# AIRZAI_BASE_BD_REVA_Sheet2.net
KiCad netlist of a schematic drawn in Altium Designer
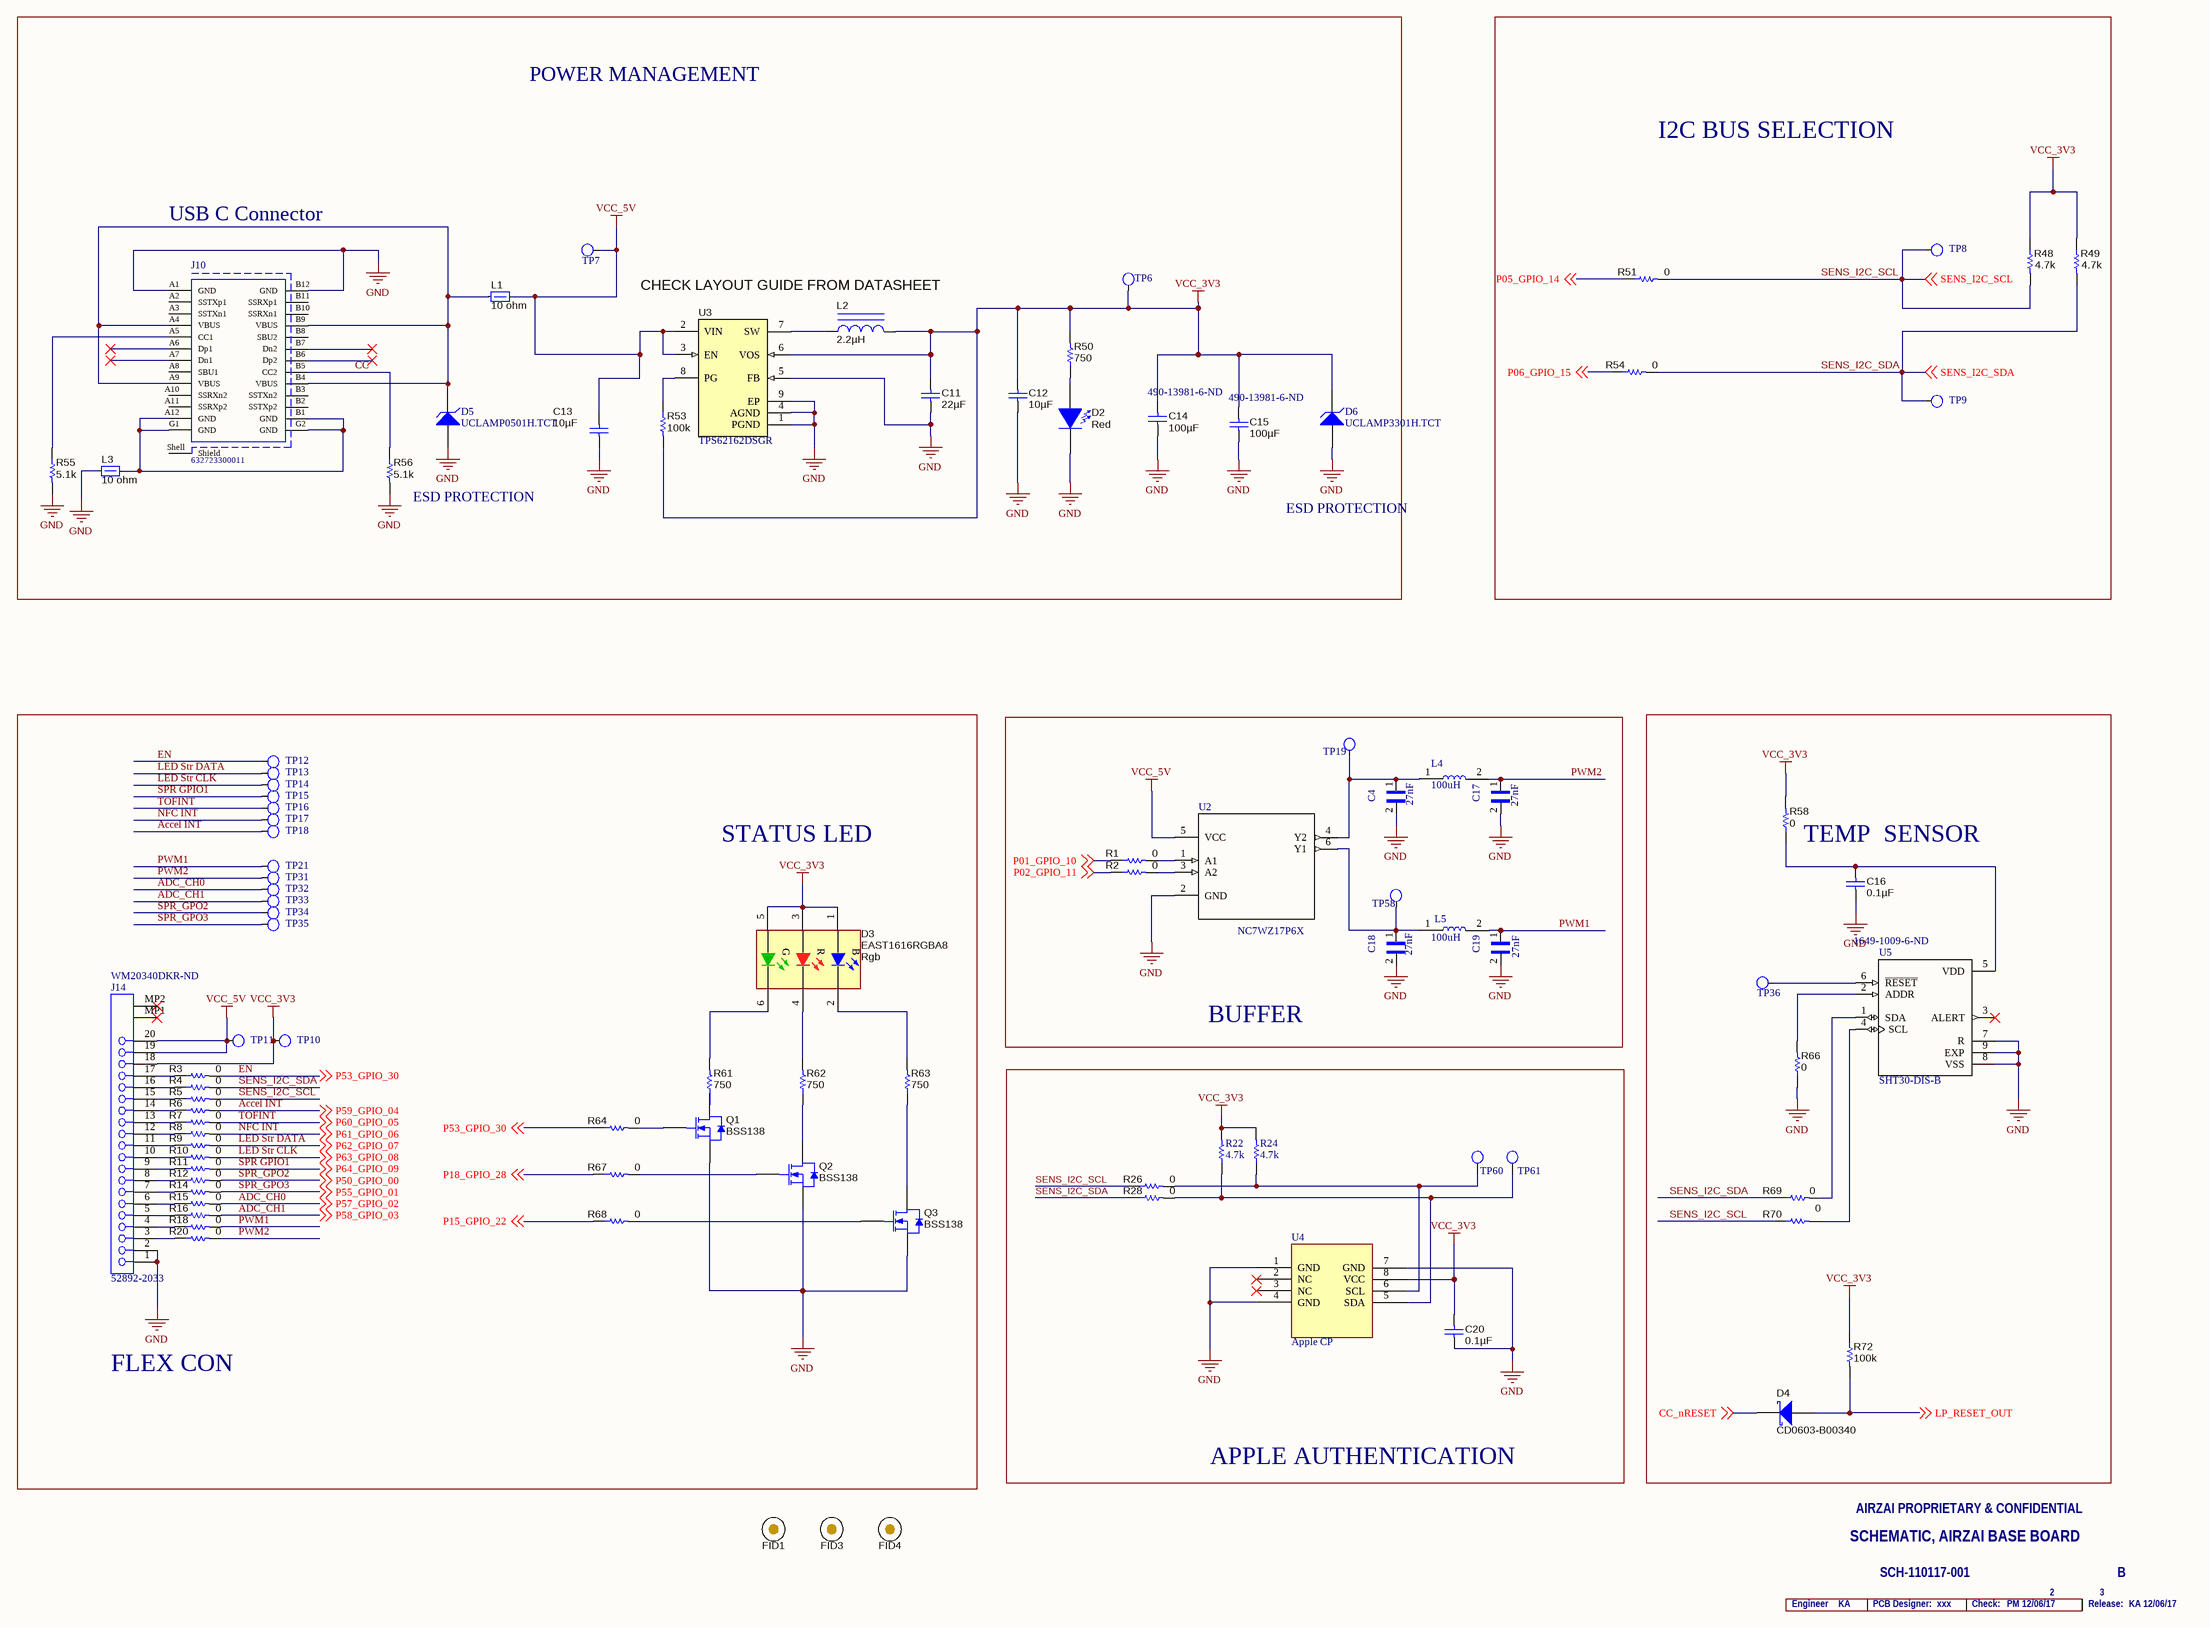
[diagram p0: AIRZAI_BASE_BD_REVA Sheet2.SchDoc]

(export (version "E")
  (design (tool "Eeschema 10.0.6"))
  (components
    (comp (ref "C4")
      (value "27nF")
      (footprint "1206CAP")
      (description "1206 27 nF 50 V Â±5% Tolerance C0G SMT Multilayer Ceramic Capacitor")
      (fields (field (name "MF") "Murata Electronics") (field (name "MP") "GRM3195C1H273JA01D"))
      (libsource (lib "GRM3195C1H273JA01D") (part "GRM3195C1H273JA01D"))
    )
    (comp (ref "C11")
      (value "C2012X5R1C226K125AC")
      (footprint "0805_HV")
      (description "CAP, CERM, 22 µF, 16 V, +/- 10%, X5R, 0805")
      (fields
        (field (name "VALUEDISPLAYED") "22µF")
        (field (name "MANUFACTURER") "TDK")
        (field (name "PUBLISHER") "Texas Instruments")
      )
      (libsource (lib "Capacitor_Ceramic") (part "C2012X5R1C226K125AC"))
    )
    (comp (ref "C12")
      (value "GRM21BR61A106KE19L")
      (footprint "0805_HV")
      (description "CAP, CERM, 10 µF, 10 V, +/- 10%, X5R, 0805")
      (fields
        (field (name "VALUEDISPLAYED") "10µF")
        (field (name "MANUFACTURER") "MuRata")
        (field (name "PUBLISHER") "Texas Instruments")
      )
      (libsource (lib "Capacitor_Ceramic") (part "GRM21BR61A106KE19L"))
    )
    (comp (ref "C13")
      (value "GRM21BR61A106KE19L")
      (footprint "0805_HV")
      (description "CAP, CERM, 10 µF, 10 V, +/- 10%, X5R, 0805")
      (fields
        (field (name "VALUEDISPLAYED") "10µF")
        (field (name "MANUFACTURER") "MuRata")
        (field (name "PUBLISHER") "Texas Instruments")
      )
      (libsource (lib "Capacitor_Ceramic") (part "GRM21BR61A106KE19L"))
    )
    (comp (ref "C14")
      (value "GRM31CR60J107ME39L")
      (footprint "1206_180")
      (description "CAP, CERM, 100 µF, 6.3 V, +/- 20%, X5R, 1206")
      (fields
        (field (name "VALUEDISPLAYED") "100µF")
        (field (name "MANUFACTURER") "MuRata")
        (field (name "SUPPLIER PART NUMBER 3") "490-13981-6-ND")
        (field (name "PUBLISHER") "Texas Instruments")
      )
      (libsource (lib "Capacitor_Ceramic") (part "GRM31CR60J107ME39L"))
    )
    (comp (ref "C15")
      (value "GRM31CR60J107ME39L")
      (footprint "1206_180")
      (description "CAP, CERM, 100 µF, 6.3 V, +/- 20%, X5R, 1206")
      (fields
        (field (name "VALUEDISPLAYED") "100µF")
        (field (name "MANUFACTURER") "MuRata")
        (field (name "SUPPLIER PART NUMBER 3") "490-13981-6-ND")
        (field (name "PUBLISHER") "Texas Instruments")
      )
      (libsource (lib "Capacitor_Ceramic") (part "GRM31CR60J107ME39L"))
    )
    (comp (ref "C16")
      (value "GRM155R61A104KA01D")
      (footprint "0402")
      (description "CAP, CERM, 0.1 µF, 10 V, +/- 10%, X5R, 0402")
      (fields
        (field (name "VALUEDISPLAYED") "0.1µF")
        (field (name "MANUFACTURER") "MuRata")
        (field (name "PUBLISHER") "Texas Instruments")
      )
      (libsource (lib "Capacitor_Ceramic") (part "GRM155R61A104KA01D"))
    )
    (comp (ref "C17")
      (value "27nF")
      (footprint "1206CAP")
      (description "1206 27 nF 50 V Â±5% Tolerance C0G SMT Multilayer Ceramic Capacitor")
      (fields (field (name "MF") "Murata Electronics") (field (name "MP") "GRM3195C1H273JA01D"))
      (libsource (lib "GRM3195C1H273JA01D") (part "GRM3195C1H273JA01D"))
    )
    (comp (ref "C18")
      (value "27nF")
      (footprint "1206CAP")
      (description "1206 27 nF 50 V Â±5% Tolerance C0G SMT Multilayer Ceramic Capacitor")
      (fields (field (name "MF") "Murata Electronics") (field (name "MP") "GRM3195C1H273JA01D"))
      (libsource (lib "GRM3195C1H273JA01D") (part "GRM3195C1H273JA01D"))
    )
    (comp (ref "C19")
      (value "27nF")
      (footprint "1206CAP")
      (description "1206 27 nF 50 V Â±5% Tolerance C0G SMT Multilayer Ceramic Capacitor")
      (fields (field (name "MF") "Murata Electronics") (field (name "MP") "GRM3195C1H273JA01D"))
      (libsource (lib "GRM3195C1H273JA01D") (part "GRM3195C1H273JA01D"))
    )
    (comp (ref "C20")
      (value "C1005X5R1A104K050BA")
      (footprint "SM0402_BTD.1SM_ACT_H55_CAP_WSS")
      (description "CAP, CERM, 0.1 µF, 10 V, +/- 10%, X5R, 0402")
      (fields
        (field (name "MANUFACTURER") "TDK")
        (field (name "VALUEDISPLAYED") "0.1µF")
        (field (name "PUBLISHER") "Texas Instruments")
      )
      (libsource (lib "AIRZAI_MBD_REVB2") (part "C1005X5R1A104K050BA"))
    )
    (comp (ref "D2")
      (value "Red")
      (footprint "SML-31_Red")
      (description "LED, Red, SMD")
      (fields
        (field (name "MANUFACTURER") "Rohm")
        (field (name "PARTNUMBER") "SML-311UTT86")
        (field (name "PUBLISHER") "Texas Instruments")
      )
      (libsource (lib "LED") (part "SML-311UTT86"))
    )
    (comp (ref "D3")
      (value "EAST1616RGBA8")
      (footprint "EAST1616_RGB")
      (description "LED, Rgb, SMD")
      (fields
        (field (name "ALTIUM_VALUE") "Rgb")
        (field (name "MANUFACTURER") "Everlight")
        (field (name "SYMBOLCREATOR") "Altium")
        (field (name "PUBLISHER") "Texas Instruments")
      )
      (libsource (lib "LED") (part "EAST1616RGBA8"))
    )
    (comp (ref "D4")
      (value "CD0603-B00340")
      (footprint "Diode_0603")
      (description "Diode, Schottky, 45 V, 0.03 A, 0603 Diode")
      (fields (field (name "MANUFACTURER") "Bourns") (field (name "PUBLISHER") "Texas Instruments"))
      (libsource (lib "Diode") (part "CD0603-B00340"))
    )
    (comp (ref "D5")
      (value "UCLAMP0501H.TCT")
      (footprint "SOD-523")
      (description "TVS DIODE 5V 12.5V SOD523")
      (fields (field (name "MANUFACTURER") "Semtech"))
      (libsource (lib "AIRZAI_BASE_BD_REVA") (part "UCLAMP0501H.TCT"))
    )
    (comp (ref "D6")
      (value "UCLAMP3301H.TCT")
      (footprint "SOD-523")
      (description "TVS DIODE 3.3V 8V SOD523")
      (fields (field (name "MANUFACTURER") "Semtech"))
      (libsource (lib "AIRZAI_BASE_BD_REVA") (part "UCLAMP3301H.TCT"))
    )
    (comp (ref "FID1")
      (value "Fiducial")
      (footprint "Fiducial10-20")
      (description "Fiducial mark.  There is nothing to buy or mount.")
      (fields (field (name "SYMBOLCREATOR") "codlsc") (field (name "PUBLISHER") "Texas Instruments"))
      (libsource (lib "MiscParts") (part "Fiducial"))
    )
    (comp (ref "FID3")
      (value "Fiducial")
      (footprint "Fiducial10-20")
      (description "Fiducial mark.  There is nothing to buy or mount.")
      (fields (field (name "SYMBOLCREATOR") "codlsc") (field (name "PUBLISHER") "Texas Instruments"))
      (libsource (lib "MiscParts") (part "Fiducial"))
    )
    (comp (ref "FID4")
      (value "Fiducial")
      (footprint "Fiducial10-20")
      (description "Fiducial mark.  There is nothing to buy or mount.")
      (fields (field (name "SYMBOLCREATOR") "codlsc") (field (name "PUBLISHER") "Texas Instruments"))
      (libsource (lib "MiscParts") (part "Fiducial"))
    )
    (comp (ref "J10")
      (value "632723300011")
      (footprint "632723300011")
      (description "USB 3.1 Type C Receptacle WR-COM, Horizontal, SMT / THT")
      (fields (field (name "PUBLISHER") "Wurth Elektronik"))
      (libsource (lib "Altium_WR-COM_USB-Connectors (rev18b)") (part "632723300011"))
    )
    (comp (ref "J14")
      (value "52892-2033")
      (footprint "MOLX-52892-2033")
      (fields (field (name "MANUFACTURER") "Molex") (field (name "SUPPLIER PART NUMBER 1") "WM20340DKR-ND"))
      (libsource (lib "Altium Content Vault") (part "MOLX-52892-2033"))
    )
    (comp (ref "L1")
      (value "10 ohm")
      (footprint "0402")
      (description "Ferrite Bead, 10 ohm @ 100 MHz, 1 A, 0402")
      (fields
        (field (name "PARTNUMBER") "BLM15AG100SN1D")
        (field (name "MANUFACTURER") "MuRata")
        (field (name "PUBLISHER") "Texas Instruments")
      )
      (libsource (lib "FerriteBead") (part "BLM15AG100SN1D"))
    )
    (comp (ref "L2")
      (value "BRC2012T2R2MD")
      (footprint "0805_HV")
      (description "Inductor, Wirewound, 2.2 µH, 1 A, 0.143 ohm, SMD")
      (fields
        (field (name "VALUEDISPLAYED") "2.2µH")
        (field (name "MANUFACTURER") "Taiyo Yuden")
        (field (name "PUBLISHER") "Texas Instruments")
      )
      (libsource (lib "Inductor_Other") (part "BRC2012T2R2MD"))
    )
    (comp (ref "L3")
      (value "10 ohm")
      (footprint "0402")
      (description "Ferrite Bead, 10 ohm @ 100 MHz, 1 A, 0402")
      (fields
        (field (name "PARTNUMBER") "BLM15AG100SN1D")
        (field (name "MANUFACTURER") "MuRata")
        (field (name "PUBLISHER") "Texas Instruments")
      )
      (libsource (lib "") (part "BLM15AG100SN1D_1"))
    )
    (comp (ref "L4")
      (value "100uH")
      (footprint "0805_Inductor")
      (description "Fixed Ind 100uh 2ma 3.1 Ohm Smd")
      (fields (field (name "MP") "MLF2012C101KTD25") (field (name "MF") "TDK"))
      (libsource (lib "MLF2012C101KTD25") (part "MLF2012C101KTD25"))
    )
    (comp (ref "L5")
      (value "100uH")
      (footprint "0805_Inductor")
      (description "Fixed Ind 100uh 2ma 3.1 Ohm Smd")
      (fields (field (name "MP") "MLF2012C101KTD25") (field (name "MF") "TDK"))
      (libsource (lib "MLF2012C101KTD25") (part "MLF2012C101KTD25"))
    )
    (comp (ref "Q1")
      (value "BSS138")
      (footprint "SOT-23")
      (description "MOSFET, N-CH, 50 V, 0.22 A, SOT-23")
      (fields
        (field (name "MANUFACTURER") "Fairchild Semiconductor")
        (field (name "PUBLISHER") "Texas Instruments")
      )
      (libsource (lib "FETs") (part "BSS138"))
    )
    (comp (ref "Q2")
      (value "BSS138")
      (footprint "SOT-23")
      (description "MOSFET, N-CH, 50 V, 0.22 A, SOT-23")
      (fields
        (field (name "MANUFACTURER") "Fairchild Semiconductor")
        (field (name "PUBLISHER") "Texas Instruments")
      )
      (libsource (lib "FETs") (part "BSS138"))
    )
    (comp (ref "Q3")
      (value "BSS138")
      (footprint "SOT-23")
      (description "MOSFET, N-CH, 50 V, 0.22 A, SOT-23")
      (fields
        (field (name "MANUFACTURER") "Fairchild Semiconductor")
        (field (name "PUBLISHER") "Texas Instruments")
      )
      (libsource (lib "FETs") (part "BSS138"))
    )
    (comp (ref "R1")
      (value "ERJ-2GE0R00X")
      (footprint "0402")
      (description "RES, 0, 5%, 0.063 W, 0402")
      (fields
        (field (name "VALUEDISPLAYED") "0")
        (field (name "MANUFACTURER") "Panasonic")
        (field (name "DIGI-KEY_PART_NUMBER") "P0.0JCT-ND")
        (field (name "PUBLISHER") "Texas Instruments")
      )
      (libsource (lib "Resistor_0402") (part "ERJ-2GE0R00X"))
    )
    (comp (ref "R2")
      (value "ERJ-2GE0R00X")
      (footprint "0402")
      (description "RES, 0, 5%, 0.063 W, 0402")
      (fields
        (field (name "VALUEDISPLAYED") "0")
        (field (name "MANUFACTURER") "Panasonic")
        (field (name "DIGI-KEY_PART_NUMBER") "P0.0JCT-ND")
        (field (name "PUBLISHER") "Texas Instruments")
      )
      (libsource (lib "Resistor_0402") (part "ERJ-2GE0R00X"))
    )
    (comp (ref "R3")
      (value "ERJ-2GE0R00X")
      (footprint "0402")
      (description "RES, 0, 5%, 0.063 W, 0402")
      (fields
        (field (name "VALUEDISPLAYED") "0")
        (field (name "MANUFACTURER") "Panasonic")
        (field (name "PUBLISHER") "Texas Instruments")
      )
      (libsource (lib "Resistor_0402") (part "ERJ-2GE0R00X"))
    )
    (comp (ref "R4")
      (value "ERJ-2GE0R00X")
      (footprint "0402")
      (description "RES, 0, 5%, 0.063 W, 0402")
      (fields
        (field (name "VALUEDISPLAYED") "0")
        (field (name "MANUFACTURER") "Panasonic")
        (field (name "PUBLISHER") "Texas Instruments")
      )
      (libsource (lib "Resistor_0402") (part "ERJ-2GE0R00X"))
    )
    (comp (ref "R5")
      (value "ERJ-2GE0R00X")
      (footprint "0402")
      (description "RES, 0, 5%, 0.063 W, 0402")
      (fields
        (field (name "VALUEDISPLAYED") "0")
        (field (name "MANUFACTURER") "Panasonic")
        (field (name "PUBLISHER") "Texas Instruments")
      )
      (libsource (lib "Resistor_0402") (part "ERJ-2GE0R00X"))
    )
    (comp (ref "R6")
      (value "ERJ-2GE0R00X")
      (footprint "0402")
      (description "RES, 0, 5%, 0.063 W, 0402")
      (fields
        (field (name "VALUEDISPLAYED") "0")
        (field (name "MANUFACTURER") "Panasonic")
        (field (name "PUBLISHER") "Texas Instruments")
      )
      (libsource (lib "Resistor_0402") (part "ERJ-2GE0R00X"))
    )
    (comp (ref "R7")
      (value "ERJ-2GE0R00X")
      (footprint "0402")
      (description "RES, 0, 5%, 0.063 W, 0402")
      (fields
        (field (name "VALUEDISPLAYED") "0")
        (field (name "MANUFACTURER") "Panasonic")
        (field (name "PUBLISHER") "Texas Instruments")
      )
      (libsource (lib "Resistor_0402") (part "ERJ-2GE0R00X"))
    )
    (comp (ref "R8")
      (value "ERJ-2GE0R00X")
      (footprint "0402")
      (description "RES, 0, 5%, 0.063 W, 0402")
      (fields
        (field (name "VALUEDISPLAYED") "0")
        (field (name "MANUFACTURER") "Panasonic")
        (field (name "PUBLISHER") "Texas Instruments")
      )
      (libsource (lib "Resistor_0402") (part "ERJ-2GE0R00X"))
    )
    (comp (ref "R9")
      (value "ERJ-2GE0R00X")
      (footprint "0402")
      (description "RES, 0, 5%, 0.063 W, 0402")
      (fields
        (field (name "VALUEDISPLAYED") "0")
        (field (name "MANUFACTURER") "Panasonic")
        (field (name "PUBLISHER") "Texas Instruments")
      )
      (libsource (lib "Resistor_0402") (part "ERJ-2GE0R00X"))
    )
    (comp (ref "R10")
      (value "ERJ-2GE0R00X")
      (footprint "0402")
      (description "RES, 0, 5%, 0.063 W, 0402")
      (fields
        (field (name "VALUEDISPLAYED") "0")
        (field (name "MANUFACTURER") "Panasonic")
        (field (name "PUBLISHER") "Texas Instruments")
      )
      (libsource (lib "Resistor_0402") (part "ERJ-2GE0R00X"))
    )
    (comp (ref "R11")
      (value "ERJ-2GE0R00X")
      (footprint "0402")
      (description "RES, 0, 5%, 0.063 W, 0402")
      (fields
        (field (name "VALUEDISPLAYED") "0")
        (field (name "MANUFACTURER") "Panasonic")
        (field (name "PUBLISHER") "Texas Instruments")
      )
      (libsource (lib "Resistor_0402") (part "ERJ-2GE0R00X"))
    )
    (comp (ref "R12")
      (value "ERJ-2GE0R00X")
      (footprint "0402")
      (description "RES, 0, 5%, 0.063 W, 0402")
      (fields
        (field (name "VALUEDISPLAYED") "0")
        (field (name "MANUFACTURER") "Panasonic")
        (field (name "PUBLISHER") "Texas Instruments")
      )
      (libsource (lib "Resistor_0402") (part "ERJ-2GE0R00X"))
    )
    (comp (ref "R14")
      (value "ERJ-2GE0R00X")
      (footprint "0402")
      (description "RES, 0, 5%, 0.063 W, 0402")
      (fields
        (field (name "VALUEDISPLAYED") "0")
        (field (name "MANUFACTURER") "Panasonic")
        (field (name "PUBLISHER") "Texas Instruments")
      )
      (libsource (lib "Resistor_0402") (part "ERJ-2GE0R00X"))
    )
    (comp (ref "R15")
      (value "ERJ-2GE0R00X")
      (footprint "0402")
      (description "RES, 0, 5%, 0.063 W, 0402")
      (fields
        (field (name "VALUEDISPLAYED") "0")
        (field (name "MANUFACTURER") "Panasonic")
        (field (name "PUBLISHER") "Texas Instruments")
      )
      (libsource (lib "Resistor_0402") (part "ERJ-2GE0R00X"))
    )
    (comp (ref "R16")
      (value "ERJ-2GE0R00X")
      (footprint "0402")
      (description "RES, 0, 5%, 0.063 W, 0402")
      (fields
        (field (name "VALUEDISPLAYED") "0")
        (field (name "MANUFACTURER") "Panasonic")
        (field (name "PUBLISHER") "Texas Instruments")
      )
      (libsource (lib "Resistor_0402") (part "ERJ-2GE0R00X"))
    )
    (comp (ref "R18")
      (value "ERJ-2GE0R00X")
      (footprint "0402")
      (description "RES, 0, 5%, 0.063 W, 0402")
      (fields
        (field (name "VALUEDISPLAYED") "0")
        (field (name "MANUFACTURER") "Panasonic")
        (field (name "PUBLISHER") "Texas Instruments")
      )
      (libsource (lib "Resistor_0402") (part "ERJ-2GE0R00X"))
    )
    (comp (ref "R20")
      (value "ERJ-2GE0R00X")
      (footprint "0402")
      (description "RES, 0, 5%, 0.063 W, 0402")
      (fields
        (field (name "VALUEDISPLAYED") "0")
        (field (name "MANUFACTURER") "Panasonic")
        (field (name "PUBLISHER") "Texas Instruments")
      )
      (libsource (lib "Resistor_0402") (part "ERJ-2GE0R00X"))
    )
    (comp (ref "R22")
      (value "RMCF0402JT4K70")
      (footprint "0402")
      (description "Chip Resistor, 4.7 KOhm, +/- 5%, 0.063 W, -55 to 155 degC, 0402 (1005 Metric), RoHS, Tape and Reel")
      (fields
        (field (name "MANUFACTURER") "Stackpole-Electronics-Inc.")
        (field (name "TOLERANCE") "±5%")
        (field (name "RESISTANCE (OHMS)") "4.7k")
      )
      (libsource (lib "AIRZAI_BASE_BD_REVA") (part "RES-2"))
    )
    (comp (ref "R24")
      (value "RMCF0402JT4K70")
      (footprint "0402")
      (description "Chip Resistor, 4.7 KOhm, +/- 5%, 0.063 W, -55 to 155 degC, 0402 (1005 Metric), RoHS, Tape and Reel")
      (fields
        (field (name "MANUFACTURER") "Stackpole-Electronics-Inc.")
        (field (name "TOLERANCE") "±5%")
        (field (name "RESISTANCE (OHMS)") "4.7k")
      )
      (libsource (lib "AIRZAI_BASE_BD_REVA") (part "RES-2"))
    )
    (comp (ref "R26")
      (value "ERJ-2GE0R00X")
      (footprint "0402")
      (description "RES, 0, 5%, 0.063 W, 0402")
      (fields
        (field (name "VALUEDISPLAYED") "0")
        (field (name "MANUFACTURER") "Panasonic")
        (field (name "DIGI-KEY_PART_NUMBER") "P0.0JCT-ND")
        (field (name "PUBLISHER") "Texas Instruments")
      )
      (libsource (lib "Resistor_0402") (part "ERJ-2GE0R00X"))
    )
    (comp (ref "R28")
      (value "ERJ-2GE0R00X")
      (footprint "0402")
      (description "RES, 0, 5%, 0.063 W, 0402")
      (fields
        (field (name "VALUEDISPLAYED") "0")
        (field (name "MANUFACTURER") "Panasonic")
        (field (name "DIGI-KEY_PART_NUMBER") "P0.0JCT-ND")
        (field (name "PUBLISHER") "Texas Instruments")
      )
      (libsource (lib "Resistor_0402") (part "ERJ-2GE0R00X"))
    )
    (comp (ref "R48")
      (value "4.7k")
      (footprint "0402")
      (description "RES SMD 4.7K OHM 1% 1/16W 0402")
      (fields
        (field (name "MANUFACTURER") "Yageo")
        (field (name "MANUFACTURER PART NUMBER") "RC0402FR-074K7L")
      )
      (libsource (lib "Resistor_0402") (part "CRCW04023K30JNED"))
    )
    (comp (ref "R49")
      (value "4.7k")
      (footprint "0402")
      (description "RES SMD 4.7K OHM 1% 1/16W 0402")
      (fields
        (field (name "MANUFACTURER") "Yageo")
        (field (name "MANUFACTURER PART NUMBER") "RC0402FR-074K7L")
      )
      (libsource (lib "Resistor_0402") (part "CRCW04023K30JNED"))
    )
    (comp (ref "R50")
      (value "RC0603JR-07750RL")
      (footprint "0603")
      (description "RES, 750, 5%, 0.1 W, 0603")
      (fields
        (field (name "VALUEDISPLAYED") "750")
        (field (name "MANUFACTURER") "Yageo America")
        (field (name "PUBLISHER") "Texas Instruments")
      )
      (libsource (lib "Resistor_0603") (part "RC0603JR-07750RL"))
    )
    (comp (ref "R51")
      (value "ERJ-2GE0R00X")
      (footprint "0402")
      (description "RES, 0, 5%, 0.063 W, 0402")
      (fields
        (field (name "VALUEDISPLAYED") "0")
        (field (name "MANUFACTURER") "Panasonic")
        (field (name "PUBLISHER") "Texas Instruments")
      )
      (libsource (lib "Resistor_0402") (part "ERJ-2GE0R00X"))
    )
    (comp (ref "R53")
      (value "CRCW0402100KJNED")
      (footprint "0402")
      (description "RES, 100 k, 5%, 0.063 W, 0402")
      (fields
        (field (name "VALUEDISPLAYED") "100k")
        (field (name "MANUFACTURER") "Vishay-Dale")
        (field (name "PUBLISHER") "Texas Instruments")
      )
      (libsource (lib "Resistor_0402") (part "CRCW0402100KJNED"))
    )
    (comp (ref "R54")
      (value "ERJ-2GE0R00X")
      (footprint "0402")
      (description "RES, 0, 5%, 0.063 W, 0402")
      (fields
        (field (name "VALUEDISPLAYED") "0")
        (field (name "MANUFACTURER") "Panasonic")
        (field (name "PUBLISHER") "Texas Instruments")
      )
      (libsource (lib "Resistor_0402") (part "ERJ-2GE0R00X"))
    )
    (comp (ref "R55")
      (value "CRCW040210K0JNED")
      (footprint "0402")
      (description "RES, 10 k, 5%, 0.063 W, 0402")
      (fields
        (field (name "VALUEDISPLAYED") "5.1k")
        (field (name "MANUFACTURER") "Vishay-Dale")
        (field (name "PUBLISHER") "Texas Instruments")
      )
      (libsource (lib "Resistor_0402") (part "CRCW040210K0JNED"))
    )
    (comp (ref "R56")
      (value "CRCW040210K0JNED")
      (footprint "0402")
      (description "RES, 10 k, 5%, 0.063 W, 0402")
      (fields
        (field (name "VALUEDISPLAYED") "5.1k")
        (field (name "MANUFACTURER") "Vishay-Dale")
        (field (name "PUBLISHER") "Texas Instruments")
      )
      (libsource (lib "Resistor_0402") (part "CRCW040210K0JNED"))
    )
    (comp (ref "R58")
      (value "ERJ-2GE0R00X")
      (footprint "0402")
      (description "RES, 0, 5%, 0.063 W, 0402")
      (fields
        (field (name "VALUEDISPLAYED") "0")
        (field (name "MANUFACTURER") "Panasonic")
        (field (name "PUBLISHER") "Texas Instruments")
      )
      (libsource (lib "Resistor_0402") (part "ERJ-2GE0R00X"))
    )
    (comp (ref "R61")
      (value "RC0603JR-07750RL")
      (footprint "0603")
      (description "RES, 750, 5%, 0.1 W, 0603")
      (fields
        (field (name "VALUEDISPLAYED") "750")
        (field (name "MANUFACTURER") "Yageo America")
        (field (name "PUBLISHER") "Texas Instruments")
      )
      (libsource (lib "Resistor_0603") (part "RC0603JR-07750RL"))
    )
    (comp (ref "R62")
      (value "RC0603JR-07750RL")
      (footprint "0603")
      (description "RES, 750, 5%, 0.1 W, 0603")
      (fields
        (field (name "VALUEDISPLAYED") "750")
        (field (name "MANUFACTURER") "Yageo America")
        (field (name "PUBLISHER") "Texas Instruments")
      )
      (libsource (lib "Resistor_0603") (part "RC0603JR-07750RL"))
    )
    (comp (ref "R63")
      (value "RC0603JR-07750RL")
      (footprint "0603")
      (description "RES, 750, 5%, 0.1 W, 0603")
      (fields
        (field (name "VALUEDISPLAYED") "750")
        (field (name "MANUFACTURER") "Yageo America")
        (field (name "PUBLISHER") "Texas Instruments")
      )
      (libsource (lib "Resistor_0603") (part "RC0603JR-07750RL"))
    )
    (comp (ref "R64")
      (value "ERJ-2GE0R00X")
      (footprint "0402")
      (description "RES, 0, 5%, 0.063 W, 0402")
      (fields
        (field (name "VALUEDISPLAYED") "0")
        (field (name "MANUFACTURER") "Panasonic")
        (field (name "PUBLISHER") "Texas Instruments")
      )
      (libsource (lib "Resistor_0402") (part "ERJ-2GE0R00X"))
    )
    (comp (ref "R66")
      (value "ERJ-2GE0R00X")
      (footprint "0402")
      (description "RES, 0, 5%, 0.063 W, 0402")
      (fields
        (field (name "VALUEDISPLAYED") "0")
        (field (name "MANUFACTURER") "Panasonic")
        (field (name "PUBLISHER") "Texas Instruments")
      )
      (libsource (lib "Resistor_0402") (part "ERJ-2GE0R00X"))
    )
    (comp (ref "R67")
      (value "ERJ-2GE0R00X")
      (footprint "0402")
      (description "RES, 0, 5%, 0.063 W, 0402")
      (fields
        (field (name "VALUEDISPLAYED") "0")
        (field (name "MANUFACTURER") "Panasonic")
        (field (name "PUBLISHER") "Texas Instruments")
      )
      (libsource (lib "Resistor_0402") (part "ERJ-2GE0R00X"))
    )
    (comp (ref "R68")
      (value "ERJ-2GE0R00X")
      (footprint "0402")
      (description "RES, 0, 5%, 0.063 W, 0402")
      (fields
        (field (name "VALUEDISPLAYED") "0")
        (field (name "MANUFACTURER") "Panasonic")
        (field (name "PUBLISHER") "Texas Instruments")
      )
      (libsource (lib "Resistor_0402") (part "ERJ-2GE0R00X"))
    )
    (comp (ref "R69")
      (value "ERJ-2GE0R00X")
      (footprint "0402")
      (description "RES, 0, 5%, 0.063 W, 0402")
      (fields
        (field (name "VALUEDISPLAYED") "0")
        (field (name "MANUFACTURER") "Panasonic")
        (field (name "PUBLISHER") "Texas Instruments")
      )
      (libsource (lib "Resistor_0402") (part "ERJ-2GE0R00X"))
    )
    (comp (ref "R70")
      (value "ERJ-2GE0R00X")
      (footprint "0402")
      (description "RES, 0, 5%, 0.063 W, 0402")
      (fields
        (field (name "VALUEDISPLAYED") "0")
        (field (name "MANUFACTURER") "Panasonic")
        (field (name "PUBLISHER") "Texas Instruments")
      )
      (libsource (lib "Resistor_0402") (part "ERJ-2GE0R00X"))
    )
    (comp (ref "R72")
      (value "CRCW0402100KJNED")
      (footprint "0402")
      (description "RES, 100 k, 5%, 0.063 W, 0402")
      (fields
        (field (name "VALUEDISPLAYED") "100k")
        (field (name "MANUFACTURER") "Vishay-Dale")
        (field (name "PUBLISHER") "Texas Instruments")
      )
      (libsource (lib "Resistor_0402") (part "CRCW0402100KJNED"))
    )
    (comp (ref "TP6")
      (value "WIREPT")
      (footprint "TP_0.9MM")
      (libsource (lib "EAGLE_CAD_Library") (part "WIREPT"))
    )
    (comp (ref "TP7")
      (value "WIREPT")
      (footprint "TP_0.9MM")
      (libsource (lib "EAGLE_CAD_Library") (part "WIREPT"))
    )
    (comp (ref "TP8")
      (value "WIREPT")
      (footprint "TP_0.9MM")
      (libsource (lib "EAGLE_CAD_Library") (part "WIREPT"))
    )
    (comp (ref "TP9")
      (value "WIREPT")
      (footprint "TP_0.9MM")
      (libsource (lib "EAGLE_CAD_Library") (part "WIREPT"))
    )
    (comp (ref "TP10")
      (value "WIREPT")
      (footprint "TP_0.9MM")
      (libsource (lib "EAGLE_CAD_Library") (part "WIREPT"))
    )
    (comp (ref "TP11")
      (value "WIREPT")
      (footprint "TP_0.9MM")
      (libsource (lib "EAGLE_CAD_Library") (part "WIREPT"))
    )
    (comp (ref "TP12")
      (value "WIREPT")
      (footprint "TP_0.9MM")
      (libsource (lib "EAGLE_CAD_Library") (part "WIREPT"))
    )
    (comp (ref "TP13")
      (value "WIREPT")
      (footprint "TP_0.9MM")
      (libsource (lib "EAGLE_CAD_Library") (part "WIREPT"))
    )
    (comp (ref "TP14")
      (value "WIREPT")
      (footprint "TP_0.9MM")
      (libsource (lib "EAGLE_CAD_Library") (part "WIREPT"))
    )
    (comp (ref "TP15")
      (value "WIREPT")
      (footprint "TP_0.9MM")
      (libsource (lib "EAGLE_CAD_Library") (part "WIREPT"))
    )
    (comp (ref "TP16")
      (value "WIREPT")
      (footprint "TP_0.9MM")
      (libsource (lib "EAGLE_CAD_Library") (part "WIREPT"))
    )
    (comp (ref "TP17")
      (value "WIREPT")
      (footprint "TP_0.9MM")
      (libsource (lib "EAGLE_CAD_Library") (part "WIREPT"))
    )
    (comp (ref "TP18")
      (value "WIREPT")
      (footprint "TP_0.9MM")
      (libsource (lib "EAGLE_CAD_Library") (part "WIREPT"))
    )
    (comp (ref "TP19")
      (value "WIREPT")
      (footprint "TP_0.9MM")
      (libsource (lib "AIRZAI_MBD_REVB") (part "WIREPT"))
    )
    (comp (ref "TP21")
      (value "WIREPT")
      (footprint "TP_0.9MM")
      (libsource (lib "EAGLE_CAD_Library") (part "WIREPT"))
    )
    (comp (ref "TP31")
      (value "WIREPT")
      (footprint "TP_0.9MM")
      (libsource (lib "EAGLE_CAD_Library") (part "WIREPT"))
    )
    (comp (ref "TP32")
      (value "WIREPT")
      (footprint "TP_0.9MM")
      (libsource (lib "EAGLE_CAD_Library") (part "WIREPT"))
    )
    (comp (ref "TP33")
      (value "WIREPT")
      (footprint "TP_0.9MM")
      (libsource (lib "EAGLE_CAD_Library") (part "WIREPT"))
    )
    (comp (ref "TP34")
      (value "WIREPT")
      (footprint "TP_0.9MM")
      (libsource (lib "EAGLE_CAD_Library") (part "WIREPT"))
    )
    (comp (ref "TP35")
      (value "WIREPT")
      (footprint "TP_0.9MM")
      (libsource (lib "EAGLE_CAD_Library") (part "WIREPT"))
    )
    (comp (ref "TP36")
      (value "WIREPT")
      (footprint "TP_0.9MM")
      (libsource (lib "EAGLE_CAD_Library") (part "WIREPT"))
    )
    (comp (ref "TP58")
      (value "WIREPT")
      (footprint "TP_0.9MM")
      (libsource (lib "AIRZAI_MBD_REVB") (part "WIREPT"))
    )
    (comp (ref "TP60")
      (value "TESTPOINT")
      (footprint "TP_0.9MM")
      (libsource (lib "AIRZAI_LID_BD_REVA") (part "TESTPOINT"))
    )
    (comp (ref "TP61")
      (value "TESTPOINT")
      (footprint "TP_0.9MM")
      (libsource (lib "AIRZAI_LID_BD_REVA") (part "TESTPOINT"))
    )
    (comp (ref "U2")
      (value "NC7WZ17P6X")
      (footprint "SC-70-NC7WZ17P6X")
      (description "NC7WZ17 Series 5.5 V TinyLogic UHS Dual Buffer w/ Schmitt Trigger Inputs-SC-70-6")
      (fields (field (name "MF") "ON Semiconductor"))
      (libsource (lib "NC7WZ17P6X") (part "NC7WZ17P6X"))
    )
    (comp (ref "U3")
      (value "TPS62162DSGR")
      (footprint "DSG0008A")
      (fields
        (field (name "MANUFACTURER") "Texas Instruments")
        (field (name "ALTERNATE PARTNUMBER") "Equivalent")
      )
      (libsource (lib "TI Power Management Step-Down Regulator") (part "TPS62162DSGR"))
    )
    (comp (ref "U4")
      (value "Apple CP")
      (footprint "XDFN-8P-Apple")
      (description "Auth 3.0 CP")
      (fields (field (name "MP") "MFI343S00177") (field (name "MF") "Apple"))
      (libsource (lib "MFI337S3959") (part "Apple CP"))
    )
    (comp (ref "U5")
      (value "SHT30-DIS-B")
      (footprint "DFN250X250X100-9N")
      (description "SHT3x Series 5.5 V Â±3 %RH 0 to 100% Temperature and Humidity Sensor - DFN-8")
      (fields (field (name "MF") "Sensirion AG") (field (name "SUPPLIER PART NUMBER 1") "1649-1009-6-ND"))
      (libsource (lib "SHT30-DIS-B") (part "SHT30-DIS-B"))
    )
  )
  (nets
    (net (code "1") (name "/CC") (class "Default")
      (node (ref "J10") (pin "B5") (pinfunction "CC2_B5") (pintype "passive"))
      (node (ref "R56") (pin "1") (pinfunction "1_1") (pintype "passive"))
    )
    (net (code "2") (name "/PWM1") (class "Default")
      (node (ref "C19") (pin "1") (pinfunction "1_1") (pintype "passive"))
      (node (ref "L5") (pin "2") (pinfunction "2_2") (pintype "passive"))
      (node (ref "R18") (pin "2") (pinfunction "2_2") (pintype "passive"))
      (node (ref "TP21") (pin "1") (pinfunction "1_1") (pintype "passive"))
    )
    (net (code "3") (name "/PWM2") (class "Default")
      (node (ref "C17") (pin "1") (pinfunction "1_1") (pintype "passive"))
      (node (ref "L4") (pin "2") (pinfunction "2_2") (pintype "passive"))
      (node (ref "R20") (pin "2") (pinfunction "2_2") (pintype "passive"))
      (node (ref "TP31") (pin "1") (pinfunction "1_1") (pintype "passive"))
    )
    (net (code "4") (name "CC_nRESET") (class "Default")
      (node (ref "D4") (pin "1") (pinfunction "K_1") (pintype "passive"))
    )
    (net (code "5") (name "GND") (class "Default")
      (node (ref "C11") (pin "2") (pinfunction "2_2") (pintype "passive"))
      (node (ref "C12") (pin "2") (pinfunction "2_2") (pintype "passive"))
      (node (ref "C13") (pin "2") (pinfunction "2_2") (pintype "passive"))
      (node (ref "C14") (pin "2") (pinfunction "2_2") (pintype "passive"))
      (node (ref "C15") (pin "2") (pinfunction "2_2") (pintype "passive"))
      (node (ref "C16") (pin "2") (pinfunction "2_2") (pintype "passive"))
      (node (ref "C17") (pin "2") (pinfunction "2_2") (pintype "passive"))
      (node (ref "C18") (pin "2") (pinfunction "2_2") (pintype "passive"))
      (node (ref "C19") (pin "2") (pinfunction "2_2") (pintype "passive"))
      (node (ref "C20") (pin "2") (pinfunction "2_2") (pintype "passive"))
      (node (ref "C4") (pin "2") (pinfunction "2_2") (pintype "passive"))
      (node (ref "D2") (pin "1") (pinfunction "K_1") (pintype "passive"))
      (node (ref "D5") (pin "A") (pinfunction "A_A") (pintype "passive"))
      (node (ref "D6") (pin "A") (pinfunction "A_A") (pintype "passive"))
      (node (ref "J10") (pin "A1") (pinfunction "GND_A1") (pintype "passive"))
      (node (ref "J10") (pin "B12") (pinfunction "GND_B12") (pintype "passive"))
      (node (ref "J14") (pin "1") (pinfunction "1_1") (pintype "passive"))
      (node (ref "J14") (pin "2") (pinfunction "2_2") (pintype "passive"))
      (node (ref "L3") (pin "2") (pinfunction "2_2") (pintype "passive"))
      (node (ref "Q1") (pin "2") (pinfunction "S_2") (pintype "passive"))
      (node (ref "Q2") (pin "2") (pinfunction "S_2") (pintype "passive"))
      (node (ref "Q3") (pin "2") (pinfunction "S_2") (pintype "passive"))
      (node (ref "R55") (pin "2") (pinfunction "2_2") (pintype "passive"))
      (node (ref "R56") (pin "2") (pinfunction "2_2") (pintype "passive"))
      (node (ref "R66") (pin "1") (pinfunction "1_1") (pintype "passive"))
      (node (ref "U2") (pin "2") (pinfunction "GND_2") (pintype "passive"))
      (node (ref "U3") (pin "1") (pinfunction "PGND_1") (pintype "power_in"))
      (node (ref "U3") (pin "4") (pinfunction "AGND_4") (pintype "power_in"))
      (node (ref "U3") (pin "5") (pinfunction "FB_5") (pintype "input"))
      (node (ref "U3") (pin "9") (pinfunction "EP_9") (pintype "power_in"))
      (node (ref "U4") (pin "1") (pinfunction "GND_1") (pintype "passive"))
      (node (ref "U4") (pin "4") (pinfunction "GND_4") (pintype "passive"))
      (node (ref "U4") (pin "7") (pinfunction "GND_7") (pintype "passive"))
      (node (ref "U5") (pin "7") (pinfunction "R_7") (pintype "passive"))
      (node (ref "U5") (pin "8") (pinfunction "VSS_8") (pintype "passive"))
      (node (ref "U5") (pin "9") (pinfunction "EXP_9") (pintype "passive"))
    )
    (net (code "6") (name "LP_RESET_OUT") (class "Default")
      (node (ref "D4") (pin "2") (pinfunction "A_2") (pintype "passive"))
      (node (ref "R72") (pin "2") (pinfunction "2_2") (pintype "passive"))
    )
    (net (code "7") (name "Net-(D2-A)") (class "Default")
      (node (ref "D2") (pin "2") (pinfunction "A_2") (pintype "passive"))
      (node (ref "R50") (pin "1") (pinfunction "1_1") (pintype "passive"))
    )
    (net (code "8") (name "Net-(D3-K-Pad2)") (class "Default")
      (node (ref "D3") (pin "2") (pinfunction "K_2") (pintype "passive"))
      (node (ref "R63") (pin "2") (pinfunction "2_2") (pintype "passive"))
    )
    (net (code "9") (name "Net-(D3-K-Pad4)") (class "Default")
      (node (ref "D3") (pin "4") (pinfunction "K_4") (pintype "passive"))
      (node (ref "R62") (pin "2") (pinfunction "2_2") (pintype "passive"))
    )
    (net (code "10") (name "Net-(D3-K-Pad6)") (class "Default")
      (node (ref "D3") (pin "6") (pinfunction "K_6") (pintype "passive"))
      (node (ref "R61") (pin "2") (pinfunction "2_2") (pintype "passive"))
    )
    (net (code "11") (name "Net-(D5-PadK)") (class "Default")
      (node (ref "D5") (pin "K") (pinfunction "K_K") (pintype "passive"))
      (node (ref "J10") (pin "A4") (pinfunction "VBUS_A4") (pintype "passive"))
      (node (ref "J10") (pin "A9") (pinfunction "VBUS_A9") (pintype "passive"))
      (node (ref "J10") (pin "B4") (pinfunction "VBUS_B4") (pintype "passive"))
      (node (ref "J10") (pin "B9") (pinfunction "VBUS_B9") (pintype "passive"))
      (node (ref "L1") (pin "1") (pinfunction "1_1") (pintype "passive"))
    )
    (net (code "12") (name "Net-(J10-CC1)") (class "Default")
      (node (ref "J10") (pin "A5") (pinfunction "CC1_A5") (pintype "passive"))
      (node (ref "R55") (pin "1") (pinfunction "1_1") (pintype "passive"))
    )
    (net (code "13") (name "Net-(J10-GND-PadA12)") (class "Default")
      (node (ref "J10") (pin "A12") (pinfunction "GND_A12") (pintype "passive"))
      (node (ref "J10") (pin "B1") (pinfunction "GND_B1") (pintype "passive"))
      (node (ref "J10") (pin "G1") (pinfunction "GND_G1") (pintype "passive"))
      (node (ref "J10") (pin "G2") (pinfunction "GND_G2") (pintype "passive"))
      (node (ref "L3") (pin "1") (pinfunction "1_1") (pintype "passive"))
    )
    (net (code "14") (name "Net-(J14-Pad3)") (class "Default")
      (node (ref "J14") (pin "3") (pinfunction "3_3") (pintype "passive"))
      (node (ref "R20") (pin "1") (pinfunction "1_1") (pintype "passive"))
    )
    (net (code "15") (name "Net-(J14-Pad4)") (class "Default")
      (node (ref "J14") (pin "4") (pinfunction "4_4") (pintype "passive"))
      (node (ref "R18") (pin "1") (pinfunction "1_1") (pintype "passive"))
    )
    (net (code "16") (name "Net-(J14-Pad5)") (class "Default")
      (node (ref "J14") (pin "5") (pinfunction "5_5") (pintype "passive"))
      (node (ref "R16") (pin "1") (pinfunction "1_1") (pintype "passive"))
    )
    (net (code "17") (name "Net-(J14-Pad6)") (class "Default")
      (node (ref "J14") (pin "6") (pinfunction "6_6") (pintype "passive"))
      (node (ref "R15") (pin "1") (pinfunction "1_1") (pintype "passive"))
    )
    (net (code "18") (name "Net-(J14-Pad7)") (class "Default")
      (node (ref "J14") (pin "7") (pinfunction "7_7") (pintype "passive"))
      (node (ref "R14") (pin "1") (pinfunction "1_1") (pintype "passive"))
    )
    (net (code "19") (name "Net-(J14-Pad8)") (class "Default")
      (node (ref "J14") (pin "8") (pinfunction "8_8") (pintype "passive"))
      (node (ref "R12") (pin "1") (pinfunction "1_1") (pintype "passive"))
    )
    (net (code "20") (name "Net-(J14-Pad9)") (class "Default")
      (node (ref "J14") (pin "9") (pinfunction "9_9") (pintype "passive"))
      (node (ref "R11") (pin "1") (pinfunction "1_1") (pintype "passive"))
    )
    (net (code "21") (name "Net-(J14-Pad10)") (class "Default")
      (node (ref "J14") (pin "10") (pinfunction "10_10") (pintype "passive"))
      (node (ref "R10") (pin "1") (pinfunction "1_1") (pintype "passive"))
    )
    (net (code "22") (name "Net-(J14-Pad11)") (class "Default")
      (node (ref "J14") (pin "11") (pinfunction "11_11") (pintype "passive"))
      (node (ref "R9") (pin "1") (pinfunction "1_1") (pintype "passive"))
    )
    (net (code "23") (name "Net-(J14-Pad12)") (class "Default")
      (node (ref "J14") (pin "12") (pinfunction "12_12") (pintype "passive"))
      (node (ref "R8") (pin "1") (pinfunction "1_1") (pintype "passive"))
    )
    (net (code "24") (name "Net-(J14-Pad13)") (class "Default")
      (node (ref "J14") (pin "13") (pinfunction "13_13") (pintype "passive"))
      (node (ref "R7") (pin "1") (pinfunction "1_1") (pintype "passive"))
    )
    (net (code "25") (name "Net-(J14-Pad14)") (class "Default")
      (node (ref "J14") (pin "14") (pinfunction "14_14") (pintype "passive"))
      (node (ref "R6") (pin "1") (pinfunction "1_1") (pintype "passive"))
    )
    (net (code "26") (name "Net-(J14-Pad15)") (class "Default")
      (node (ref "J14") (pin "15") (pinfunction "15_15") (pintype "passive"))
      (node (ref "R5") (pin "1") (pinfunction "1_1") (pintype "passive"))
    )
    (net (code "27") (name "Net-(J14-Pad16)") (class "Default")
      (node (ref "J14") (pin "16") (pinfunction "16_16") (pintype "passive"))
      (node (ref "R4") (pin "1") (pinfunction "1_1") (pintype "passive"))
    )
    (net (code "28") (name "Net-(J14-Pad17)") (class "Default")
      (node (ref "J14") (pin "17") (pinfunction "17_17") (pintype "passive"))
      (node (ref "R3") (pin "1") (pinfunction "1_1") (pintype "passive"))
    )
    (net (code "29") (name "Net-(Q1-D)") (class "Default")
      (node (ref "Q1") (pin "3") (pinfunction "D_3") (pintype "passive"))
      (node (ref "R61") (pin "1") (pinfunction "1_1") (pintype "passive"))
    )
    (net (code "30") (name "Net-(Q1-G)") (class "Default")
      (node (ref "Q1") (pin "1") (pinfunction "G_1") (pintype "passive"))
      (node (ref "R64") (pin "2") (pinfunction "2_2") (pintype "passive"))
    )
    (net (code "31") (name "Net-(Q2-D)") (class "Default")
      (node (ref "Q2") (pin "3") (pinfunction "D_3") (pintype "passive"))
      (node (ref "R62") (pin "1") (pinfunction "1_1") (pintype "passive"))
    )
    (net (code "32") (name "Net-(Q2-G)") (class "Default")
      (node (ref "Q2") (pin "1") (pinfunction "G_1") (pintype "passive"))
      (node (ref "R67") (pin "2") (pinfunction "2_2") (pintype "passive"))
    )
    (net (code "33") (name "Net-(Q3-D)") (class "Default")
      (node (ref "Q3") (pin "3") (pinfunction "D_3") (pintype "passive"))
      (node (ref "R63") (pin "1") (pinfunction "1_1") (pintype "passive"))
    )
    (net (code "34") (name "Net-(Q3-G)") (class "Default")
      (node (ref "Q3") (pin "1") (pinfunction "G_1") (pintype "passive"))
      (node (ref "R68") (pin "2") (pinfunction "2_2") (pintype "passive"))
    )
    (net (code "35") (name "Net-(U2-A1)") (class "Default")
      (node (ref "R1") (pin "2") (pinfunction "2_2") (pintype "passive"))
      (node (ref "U2") (pin "1") (pinfunction "A1_1") (pintype "input"))
    )
    (net (code "36") (name "Net-(U2-A2)") (class "Default")
      (node (ref "R2") (pin "2") (pinfunction "2_2") (pintype "passive"))
      (node (ref "U2") (pin "3") (pinfunction "A2_3") (pintype "input"))
    )
    (net (code "37") (name "Net-(U2-Y1)") (class "Default")
      (node (ref "C18") (pin "1") (pinfunction "1_1") (pintype "passive"))
      (node (ref "L5") (pin "1") (pinfunction "1_1") (pintype "passive"))
      (node (ref "TP58") (pin "1") (pinfunction "1_1") (pintype "passive"))
      (node (ref "U2") (pin "6") (pinfunction "Y1_6") (pintype "output"))
    )
    (net (code "38") (name "Net-(U2-Y2)") (class "Default")
      (node (ref "C4") (pin "1") (pinfunction "1_1") (pintype "passive"))
      (node (ref "L4") (pin "1") (pinfunction "1_1") (pintype "passive"))
      (node (ref "TP19") (pin "1") (pinfunction "1_1") (pintype "passive"))
      (node (ref "U2") (pin "4") (pinfunction "Y2_4") (pintype "output"))
    )
    (net (code "39") (name "Net-(U3-PG)") (class "Default")
      (node (ref "R53") (pin "1") (pinfunction "1_1") (pintype "passive"))
      (node (ref "U3") (pin "8") (pinfunction "PG_8") (pintype "tri_state"))
    )
    (net (code "40") (name "Net-(U3-SW)") (class "Default")
      (node (ref "L2") (pin "1") (pinfunction "1_1") (pintype "passive"))
      (node (ref "U3") (pin "7") (pinfunction "SW_7") (pintype "power_in"))
    )
    (net (code "41") (name "Net-(U4-SCL)") (class "Default")
      (node (ref "R24") (pin "1") (pinfunction "1_1") (pintype "passive"))
      (node (ref "R26") (pin "2") (pinfunction "2_2") (pintype "passive"))
      (node (ref "TP60") (pin "1") (pinfunction "1_1") (pintype "passive"))
      (node (ref "U4") (pin "6") (pinfunction "SCL_6") (pintype "passive"))
    )
    (net (code "42") (name "Net-(U4-SDA)") (class "Default")
      (node (ref "R22") (pin "1") (pinfunction "1_1") (pintype "passive"))
      (node (ref "R28") (pin "2") (pinfunction "2_2") (pintype "passive"))
      (node (ref "TP61") (pin "1") (pinfunction "1_1") (pintype "passive"))
      (node (ref "U4") (pin "5") (pinfunction "SDA_5") (pintype "passive"))
    )
    (net (code "43") (name "Net-(U5-ADDR)") (class "Default")
      (node (ref "R66") (pin "2") (pinfunction "2_2") (pintype "passive"))
      (node (ref "U5") (pin "2") (pinfunction "ADDR_2") (pintype "input"))
    )
    (net (code "44") (name "Net-(U5-SCL)") (class "Default")
      (node (ref "R70") (pin "2") (pinfunction "2_2") (pintype "passive"))
      (node (ref "U5") (pin "4") (pinfunction "SCL_4") (pintype "bidirectional"))
    )
    (net (code "45") (name "Net-(U5-SDA)") (class "Default")
      (node (ref "R69") (pin "2") (pinfunction "2_2") (pintype "passive"))
      (node (ref "U5") (pin "1") (pinfunction "SDA_1") (pintype "bidirectional"))
    )
    (net (code "46") (name "Net-(U5-VDD)") (class "Default")
      (node (ref "C16") (pin "1") (pinfunction "1_1") (pintype "passive"))
      (node (ref "R58") (pin "1") (pinfunction "1_1") (pintype "passive"))
      (node (ref "U5") (pin "5") (pinfunction "VDD_5") (pintype "power_in"))
    )
    (net (code "47") (name "Net-(U5-~{RESET})") (class "Default")
      (node (ref "TP36") (pin "1") (pinfunction "1_1") (pintype "passive"))
      (node (ref "U5") (pin "6") (pinfunction "~{RESET}_6") (pintype "input"))
    )
    (net (code "48") (name "P01_GPIO_10") (class "Default")
      (node (ref "R1") (pin "1") (pinfunction "1_1") (pintype "passive"))
    )
    (net (code "49") (name "P02_GPIO_11") (class "Default")
      (node (ref "R2") (pin "1") (pinfunction "1_1") (pintype "passive"))
    )
    (net (code "50") (name "P05_GPIO_14") (class "Default")
      (node (ref "R51") (pin "1") (pinfunction "1_1") (pintype "passive"))
    )
    (net (code "51") (name "P06_GPIO_15") (class "Default")
      (node (ref "R54") (pin "1") (pinfunction "1_1") (pintype "passive"))
    )
    (net (code "52") (name "P15_GPIO_22") (class "Default")
      (node (ref "R68") (pin "1") (pinfunction "1_1") (pintype "passive"))
    )
    (net (code "53") (name "P18_GPIO_28") (class "Default")
      (node (ref "R67") (pin "1") (pinfunction "1_1") (pintype "passive"))
    )
    (net (code "54") (name "P50_GPIO_00") (class "Default")
      (node (ref "R12") (pin "2") (pinfunction "2_2") (pintype "passive"))
      (node (ref "TP34") (pin "1") (pinfunction "1_1") (pintype "passive"))
    )
    (net (code "55") (name "P53_GPIO_30") (class "Default")
      (node (ref "R3") (pin "2") (pinfunction "2_2") (pintype "passive"))
      (node (ref "R64") (pin "1") (pinfunction "1_1") (pintype "passive"))
      (node (ref "TP12") (pin "1") (pinfunction "1_1") (pintype "passive"))
    )
    (net (code "56") (name "P55_GPIO_01") (class "Default")
      (node (ref "R14") (pin "2") (pinfunction "2_2") (pintype "passive"))
      (node (ref "TP35") (pin "1") (pinfunction "1_1") (pintype "passive"))
    )
    (net (code "57") (name "P57_GPIO_02") (class "Default")
      (node (ref "R15") (pin "2") (pinfunction "2_2") (pintype "passive"))
      (node (ref "TP32") (pin "1") (pinfunction "1_1") (pintype "passive"))
    )
    (net (code "58") (name "P58_GPIO_03") (class "Default")
      (node (ref "R16") (pin "2") (pinfunction "2_2") (pintype "passive"))
      (node (ref "TP33") (pin "1") (pinfunction "1_1") (pintype "passive"))
    )
    (net (code "59") (name "P59_GPIO_04") (class "Default")
      (node (ref "R6") (pin "2") (pinfunction "2_2") (pintype "passive"))
      (node (ref "TP18") (pin "1") (pinfunction "1_1") (pintype "passive"))
    )
    (net (code "60") (name "P60_GPIO_05") (class "Default")
      (node (ref "R7") (pin "2") (pinfunction "2_2") (pintype "passive"))
      (node (ref "TP16") (pin "1") (pinfunction "1_1") (pintype "passive"))
    )
    (net (code "61") (name "P61_GPIO_06") (class "Default")
      (node (ref "R8") (pin "2") (pinfunction "2_2") (pintype "passive"))
      (node (ref "TP17") (pin "1") (pinfunction "1_1") (pintype "passive"))
    )
    (net (code "62") (name "P62_GPIO_07") (class "Default")
      (node (ref "R9") (pin "2") (pinfunction "2_2") (pintype "passive"))
      (node (ref "TP13") (pin "1") (pinfunction "1_1") (pintype "passive"))
    )
    (net (code "63") (name "P63_GPIO_08") (class "Default")
      (node (ref "R10") (pin "2") (pinfunction "2_2") (pintype "passive"))
      (node (ref "TP14") (pin "1") (pinfunction "1_1") (pintype "passive"))
    )
    (net (code "64") (name "P64_GPIO_09") (class "Default")
      (node (ref "R11") (pin "2") (pinfunction "2_2") (pintype "passive"))
      (node (ref "TP15") (pin "1") (pinfunction "1_1") (pintype "passive"))
    )
    (net (code "65") (name "SENS_I2C_SCL") (class "Default")
      (node (ref "R26") (pin "1") (pinfunction "1_1") (pintype "passive"))
      (node (ref "R48") (pin "2") (pinfunction "2_2") (pintype "passive"))
      (node (ref "R5") (pin "2") (pinfunction "2_2") (pintype "passive"))
      (node (ref "R51") (pin "2") (pinfunction "2_2") (pintype "passive"))
      (node (ref "R70") (pin "1") (pinfunction "1_1") (pintype "passive"))
      (node (ref "TP8") (pin "1") (pinfunction "1_1") (pintype "passive"))
    )
    (net (code "66") (name "SENS_I2C_SDA") (class "Default")
      (node (ref "R28") (pin "1") (pinfunction "1_1") (pintype "passive"))
      (node (ref "R4") (pin "2") (pinfunction "2_2") (pintype "passive"))
      (node (ref "R49") (pin "2") (pinfunction "2_2") (pintype "passive"))
      (node (ref "R54") (pin "2") (pinfunction "2_2") (pintype "passive"))
      (node (ref "R69") (pin "1") (pinfunction "1_1") (pintype "passive"))
      (node (ref "TP9") (pin "1") (pinfunction "1_1") (pintype "passive"))
    )
    (net (code "67") (name "VCC_3V3") (class "Default")
      (node (ref "C11") (pin "1") (pinfunction "1_1") (pintype "passive"))
      (node (ref "C12") (pin "1") (pinfunction "1_1") (pintype "passive"))
      (node (ref "C14") (pin "1") (pinfunction "1_1") (pintype "passive"))
      (node (ref "C15") (pin "1") (pinfunction "1_1") (pintype "passive"))
      (node (ref "C20") (pin "1") (pinfunction "1_1") (pintype "passive"))
      (node (ref "D3") (pin "1") (pinfunction "A_1") (pintype "passive"))
      (node (ref "D3") (pin "3") (pinfunction "A_3") (pintype "passive"))
      (node (ref "D3") (pin "5") (pinfunction "A_5") (pintype "passive"))
      (node (ref "D6") (pin "K") (pinfunction "K_K") (pintype "passive"))
      (node (ref "J14") (pin "18") (pinfunction "18_18") (pintype "passive"))
      (node (ref "L2") (pin "2") (pinfunction "2_2") (pintype "passive"))
      (node (ref "R22") (pin "2") (pinfunction "2_2") (pintype "passive"))
      (node (ref "R24") (pin "2") (pinfunction "2_2") (pintype "passive"))
      (node (ref "R48") (pin "1") (pinfunction "1_1") (pintype "passive"))
      (node (ref "R49") (pin "1") (pinfunction "1_1") (pintype "passive"))
      (node (ref "R50") (pin "2") (pinfunction "2_2") (pintype "passive"))
      (node (ref "R53") (pin "2") (pinfunction "2_2") (pintype "passive"))
      (node (ref "R58") (pin "2") (pinfunction "2_2") (pintype "passive"))
      (node (ref "R72") (pin "1") (pinfunction "1_1") (pintype "passive"))
      (node (ref "TP10") (pin "1") (pinfunction "1_1") (pintype "passive"))
      (node (ref "TP6") (pin "1") (pinfunction "1_1") (pintype "passive"))
      (node (ref "U3") (pin "6") (pinfunction "VOS_6") (pintype "input"))
      (node (ref "U4") (pin "8") (pinfunction "VCC_8") (pintype "passive"))
    )
    (net (code "68") (name "VCC_5V") (class "Default")
      (node (ref "C13") (pin "1") (pinfunction "1_1") (pintype "passive"))
      (node (ref "J14") (pin "19") (pinfunction "19_19") (pintype "passive"))
      (node (ref "J14") (pin "20") (pinfunction "20_20") (pintype "passive"))
      (node (ref "L1") (pin "2") (pinfunction "2_2") (pintype "passive"))
      (node (ref "TP11") (pin "1") (pinfunction "1_1") (pintype "passive"))
      (node (ref "TP7") (pin "1") (pinfunction "1_1") (pintype "passive"))
      (node (ref "U2") (pin "5") (pinfunction "VCC_5") (pintype "power_in"))
      (node (ref "U3") (pin "2") (pinfunction "VIN_2") (pintype "power_in"))
      (node (ref "U3") (pin "3") (pinfunction "EN_3") (pintype "input"))
    )
    (net (code "69") (name "unconnected-(J10-Dn1-PadA7)") (class "Default")
      (node (ref "J10") (pin "A7") (pinfunction "Dn1_A7") (pintype "passive+no_connect"))
    )
    (net (code "70") (name "unconnected-(J10-Dn2-PadB7)") (class "Default")
      (node (ref "J10") (pin "B7") (pinfunction "Dn2_B7") (pintype "passive+no_connect"))
    )
    (net (code "71") (name "unconnected-(J10-Dp1-PadA6)") (class "Default")
      (node (ref "J10") (pin "A6") (pinfunction "Dp1_A6") (pintype "passive+no_connect"))
    )
    (net (code "72") (name "unconnected-(J10-Dp2-PadB6)") (class "Default")
      (node (ref "J10") (pin "B6") (pinfunction "Dp2_B6") (pintype "passive+no_connect"))
    )
    (net (code "73") (name "unconnected-(J10-SBU1-PadA8)") (class "Default")
      (node (ref "J10") (pin "A8") (pinfunction "SBU1_A8") (pintype "passive"))
    )
    (net (code "74") (name "unconnected-(J10-SBU2-PadB8)") (class "Default")
      (node (ref "J10") (pin "B8") (pinfunction "SBU2_B8") (pintype "passive"))
    )
    (net (code "75") (name "unconnected-(J10-SSRXn1-PadB10)") (class "Default")
      (node (ref "J10") (pin "B10") (pinfunction "SSRXn1_B10") (pintype "passive"))
    )
    (net (code "76") (name "unconnected-(J10-SSRXn2-PadA10)") (class "Default")
      (node (ref "J10") (pin "A10") (pinfunction "SSRXn2_A10") (pintype "passive"))
    )
    (net (code "77") (name "unconnected-(J10-SSRXp1-PadB11)") (class "Default")
      (node (ref "J10") (pin "B11") (pinfunction "SSRXp1_B11") (pintype "passive"))
    )
    (net (code "78") (name "unconnected-(J10-SSRXp2-PadA11)") (class "Default")
      (node (ref "J10") (pin "A11") (pinfunction "SSRXp2_A11") (pintype "passive"))
    )
    (net (code "79") (name "unconnected-(J10-SSTXn1-PadA3)") (class "Default")
      (node (ref "J10") (pin "A3") (pinfunction "SSTXn1_A3") (pintype "passive"))
    )
    (net (code "80") (name "unconnected-(J10-SSTXn2-PadB3)") (class "Default")
      (node (ref "J10") (pin "B3") (pinfunction "SSTXn2_B3") (pintype "passive"))
    )
    (net (code "81") (name "unconnected-(J10-SSTXp1-PadA2)") (class "Default")
      (node (ref "J10") (pin "A2") (pinfunction "SSTXp1_A2") (pintype "passive"))
    )
    (net (code "82") (name "unconnected-(J10-SSTXp2-PadB2)") (class "Default")
      (node (ref "J10") (pin "B2") (pinfunction "SSTXp2_B2") (pintype "passive"))
    )
    (net (code "83") (name "unconnected-(J10-Shield-PadShell)") (class "Default")
      (node (ref "J10") (pin "Shell") (pinfunction "Shield_Shell") (pintype "passive"))
    )
    (net (code "84") (name "unconnected-(J14-PadMP1)") (class "Default")
      (node (ref "J14") (pin "MP1") (pinfunction "MP1_MP1") (pintype "passive+no_connect"))
    )
    (net (code "85") (name "unconnected-(J14-PadMP2)") (class "Default")
      (node (ref "J14") (pin "MP2") (pinfunction "MP2_MP2") (pintype "passive+no_connect"))
    )
    (net (code "86") (name "unconnected-(U4-NC-Pad2)") (class "Default")
      (node (ref "U4") (pin "2") (pinfunction "NC_2") (pintype "passive+no_connect"))
    )
    (net (code "87") (name "unconnected-(U4-NC-Pad3)") (class "Default")
      (node (ref "U4") (pin "3") (pinfunction "NC_3") (pintype "passive+no_connect"))
    )
    (net (code "88") (name "unconnected-(U5-ALERT-Pad3)") (class "Default")
      (node (ref "U5") (pin "3") (pinfunction "ALERT_3") (pintype "output+no_connect"))
    )
  )
)
